# button_brightness_esp32.net
KiCad netlist of a schematic drawn in Altium Designer
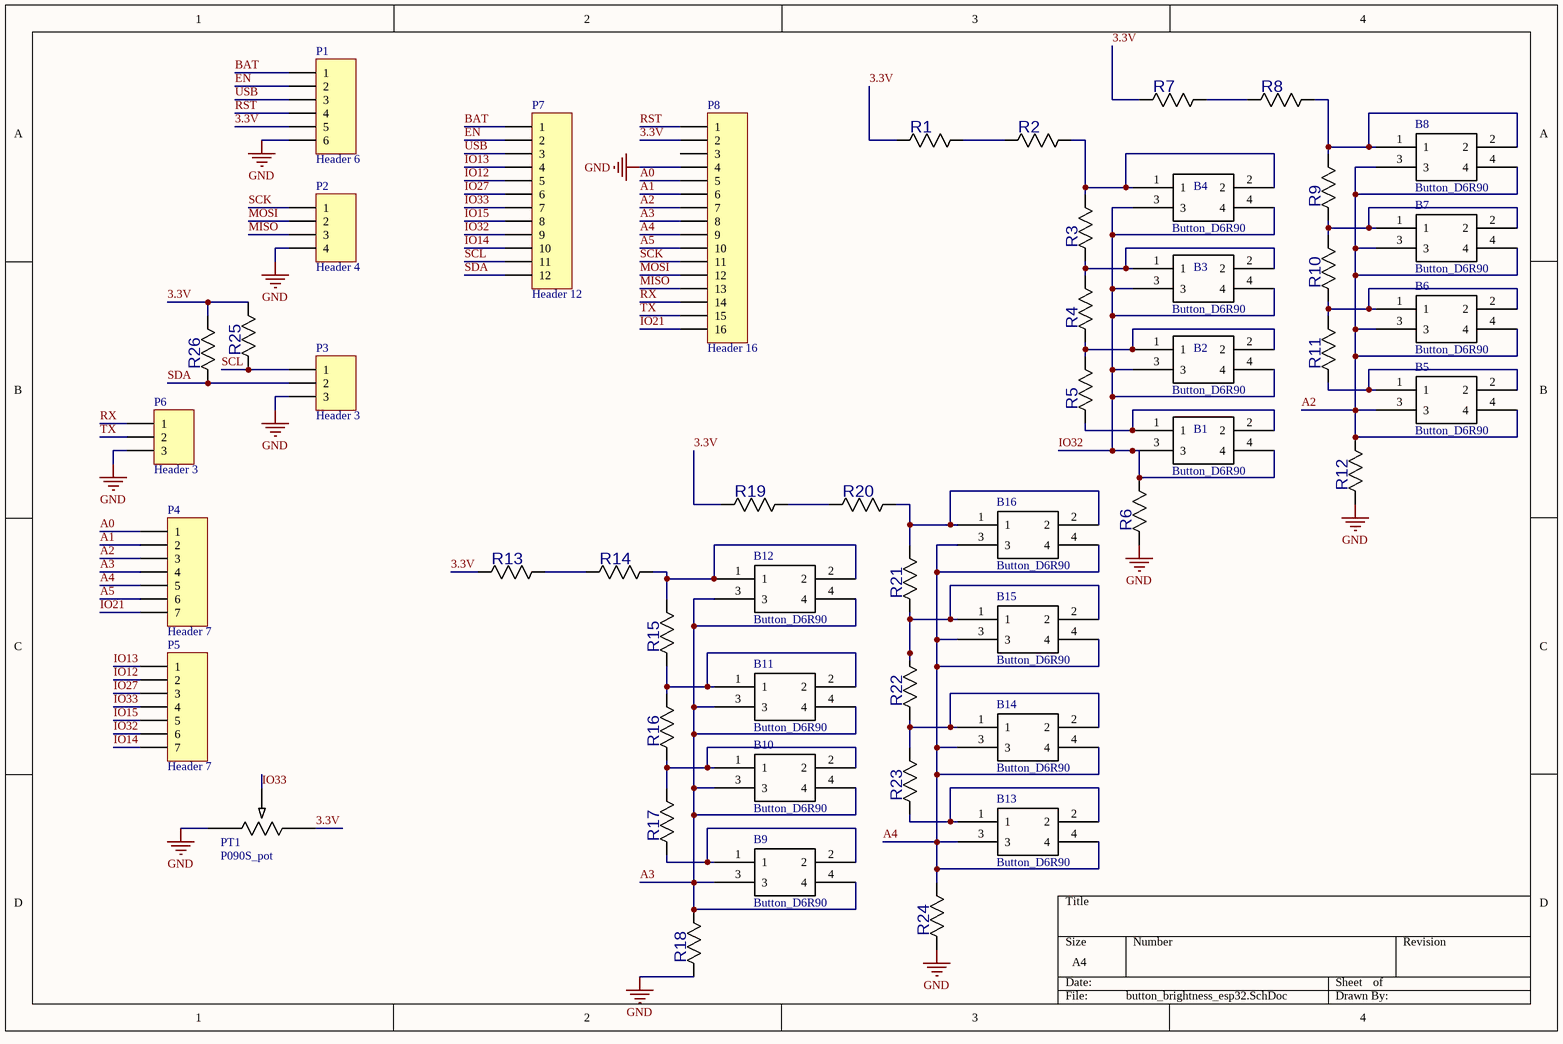
[diagram p0: button_brightness_esp32.SchDoc]

(export (version "E")
  (design (tool "Eeschema 10.0.6"))
  (components
    (comp (ref "B1")
      (value "Button_D6R90")
      (footprint "Button_D6R90")
      (libsource (lib "shematic_lib") (part "Button_D6R90"))
    )
    (comp (ref "B2")
      (value "Button_D6R90")
      (footprint "Button_D6R90")
      (libsource (lib "shematic_lib") (part "Button_D6R90"))
    )
    (comp (ref "B3")
      (value "Button_D6R90")
      (footprint "Button_D6R90")
      (libsource (lib "shematic_lib") (part "Button_D6R90"))
    )
    (comp (ref "B4")
      (value "Button_D6R90")
      (footprint "Button_D6R90")
      (libsource (lib "shematic_lib") (part "Button_D6R90"))
    )
    (comp (ref "B5")
      (value "Button_D6R90")
      (footprint "Button_D6R90")
      (libsource (lib "shematic_lib") (part "Button_D6R90"))
    )
    (comp (ref "B6")
      (value "Button_D6R90")
      (footprint "Button_D6R90")
      (libsource (lib "shematic_lib") (part "Button_D6R90"))
    )
    (comp (ref "B7")
      (value "Button_D6R90")
      (footprint "Button_D6R90")
      (libsource (lib "shematic_lib") (part "Button_D6R90"))
    )
    (comp (ref "B8")
      (value "Button_D6R90")
      (footprint "Button_D6R90")
      (libsource (lib "shematic_lib") (part "Button_D6R90"))
    )
    (comp (ref "B9")
      (value "Button_D6R90")
      (footprint "Button_D6R90")
      (libsource (lib "shematic_lib") (part "Button_D6R90"))
    )
    (comp (ref "B10")
      (value "Button_D6R90")
      (footprint "Button_D6R90")
      (libsource (lib "shematic_lib") (part "Button_D6R90"))
    )
    (comp (ref "B11")
      (value "Button_D6R90")
      (footprint "Button_D6R90")
      (libsource (lib "shematic_lib") (part "Button_D6R90"))
    )
    (comp (ref "B12")
      (value "Button_D6R90")
      (footprint "component_lib:Button_D6R90")
      (libsource (lib "shematic_lib") (part "Button_D6R90"))
    )
    (comp (ref "B13")
      (value "Button_D6R90")
      (footprint "Button_D6R90")
      (libsource (lib "shematic_lib") (part "Button_D6R90"))
    )
    (comp (ref "B14")
      (value "Button_D6R90")
      (footprint "Button_D6R90")
      (libsource (lib "shematic_lib") (part "Button_D6R90"))
    )
    (comp (ref "B15")
      (value "Button_D6R90")
      (footprint "Button_D6R90")
      (libsource (lib "shematic_lib") (part "Button_D6R90"))
    )
    (comp (ref "B16")
      (value "Button_D6R90")
      (footprint "Button_D6R90")
      (libsource (lib "shematic_lib") (part "Button_D6R90"))
    )
    (comp (ref "P1")
      (value "Header 6")
      (footprint "CONN_6")
      (description "Header, 6-Pin")
      (fields (field (name "PUBLISHER") "Altium Limited"))
      (libsource (lib "Miscellaneous Connectors") (part "Header 6"))
    )
    (comp (ref "P2")
      (value "Header 4")
      (footprint "CONN_4")
      (description "Header, 4-Pin")
      (fields (field (name "PUBLISHER") "Altium Limited"))
      (libsource (lib "Miscellaneous Connectors") (part "Header 4"))
    )
    (comp (ref "P3")
      (value "Header 3")
      (footprint "CONN_3")
      (description "Header, 3-Pin")
      (fields (field (name "PUBLISHER") "Altium Limited"))
      (libsource (lib "Miscellaneous Connectors") (part "Header 3"))
    )
    (comp (ref "P4")
      (value "Header 7")
      (footprint "CONN_7")
      (description "Header, 7-Pin")
      (fields (field (name "PUBLISHER") "Altium Limited"))
      (libsource (lib "Miscellaneous Connectors") (part "Header 7"))
    )
    (comp (ref "P5")
      (value "Header 7")
      (footprint "CONN_7")
      (description "Header, 7-Pin")
      (fields (field (name "PUBLISHER") "Altium Limited"))
      (libsource (lib "Miscellaneous Connectors") (part "Header 7"))
    )
    (comp (ref "P6")
      (value "Header 3")
      (footprint "CONN_3")
      (description "Header, 3-Pin")
      (fields (field (name "PUBLISHER") "Altium Limited"))
      (libsource (lib "Miscellaneous Connectors") (part "Header 3"))
    )
    (comp (ref "P7")
      (value "Header 12")
      (footprint "ESP32_feather_short_pins")
      (description "Header, 12-Pin")
      (fields (field (name "PUBLISHER") "Altium Limited"))
      (libsource (lib "Miscellaneous Connectors") (part "Header 12"))
    )
    (comp (ref "P8")
      (value "Header 16")
      (footprint "ESP32_feather_long_pins")
      (description "Header, 16-Pin")
      (fields (field (name "PUBLISHER") "Altium Limited"))
      (libsource (lib "Miscellaneous Connectors") (part "Header 16"))
    )
    (comp (ref "PT1")
      (value "P090S_pot")
      (footprint "POT_PTA3043")
      (libsource (lib "shematic_lib") (part "P090S_pot"))
    )
    (comp (ref "R1")
      (value "ERJ-6GEYJ471V")
      (footprint "component_lib:RES_0804_panasonic")
      (libsource (lib "shematic_lib") (part "ERJ-6GEYJ471V"))
    )
    (comp (ref "R2")
      (value "ERJ-6GEYJ471V")
      (footprint "component_lib:RES_0804_panasonic")
      (libsource (lib "shematic_lib") (part "ERJ-6GEYJ471V"))
    )
    (comp (ref "R3")
      (value "ERJ-6GEYJ471V")
      (footprint "component_lib:RES_0804_panasonic")
      (libsource (lib "shematic_lib") (part "ERJ-6GEYJ471V"))
    )
    (comp (ref "R4")
      (value "ERJ-6GEYJ471V")
      (footprint "component_lib:RES_0804_panasonic")
      (libsource (lib "shematic_lib") (part "ERJ-6GEYJ471V"))
    )
    (comp (ref "R5")
      (value "ERJ-6GEYJ471V")
      (footprint "component_lib:RES_0804_panasonic")
      (libsource (lib "shematic_lib") (part "ERJ-6GEYJ471V"))
    )
    (comp (ref "R6")
      (value "ERJ-6GEYJ471V")
      (footprint "component_lib:RES_0804_panasonic")
      (libsource (lib "shematic_lib") (part "ERJ-6GEYJ471V"))
    )
    (comp (ref "R7")
      (value "ERJ-6GEYJ471V")
      (footprint "component_lib:RES_0804_panasonic")
      (libsource (lib "shematic_lib") (part "ERJ-6GEYJ471V"))
    )
    (comp (ref "R8")
      (value "ERJ-6GEYJ471V")
      (footprint "component_lib:RES_0804_panasonic")
      (libsource (lib "shematic_lib") (part "ERJ-6GEYJ471V"))
    )
    (comp (ref "R9")
      (value "ERJ-6GEYJ471V")
      (footprint "component_lib:RES_0804_panasonic")
      (libsource (lib "shematic_lib") (part "ERJ-6GEYJ471V"))
    )
    (comp (ref "R10")
      (value "ERJ-6GEYJ471V")
      (footprint "component_lib:RES_0804_panasonic")
      (libsource (lib "shematic_lib") (part "ERJ-6GEYJ471V"))
    )
    (comp (ref "R11")
      (value "ERJ-6GEYJ471V")
      (footprint "component_lib:RES_0804_panasonic")
      (libsource (lib "shematic_lib") (part "ERJ-6GEYJ471V"))
    )
    (comp (ref "R12")
      (value "ERJ-6GEYJ471V")
      (footprint "component_lib:RES_0804_panasonic")
      (libsource (lib "shematic_lib") (part "ERJ-6GEYJ471V"))
    )
    (comp (ref "R13")
      (value "ERJ-6GEYJ471V")
      (footprint "component_lib:RES_0804_panasonic")
      (libsource (lib "shematic_lib") (part "ERJ-6GEYJ471V"))
    )
    (comp (ref "R14")
      (value "ERJ-6GEYJ471V")
      (footprint "component_lib:RES_0804_panasonic")
      (libsource (lib "shematic_lib") (part "ERJ-6GEYJ471V"))
    )
    (comp (ref "R15")
      (value "ERJ-6GEYJ471V")
      (footprint "component_lib:RES_0804_panasonic")
      (libsource (lib "shematic_lib") (part "ERJ-6GEYJ471V"))
    )
    (comp (ref "R16")
      (value "ERJ-6GEYJ471V")
      (footprint "component_lib:RES_0804_panasonic")
      (libsource (lib "shematic_lib") (part "ERJ-6GEYJ471V"))
    )
    (comp (ref "R17")
      (value "ERJ-6GEYJ471V")
      (footprint "component_lib:RES_0804_panasonic")
      (libsource (lib "shematic_lib") (part "ERJ-6GEYJ471V"))
    )
    (comp (ref "R18")
      (value "ERJ-6GEYJ471V")
      (footprint "component_lib:RES_0804_panasonic")
      (libsource (lib "shematic_lib") (part "ERJ-6GEYJ471V"))
    )
    (comp (ref "R19")
      (value "ERJ-6GEYJ471V")
      (footprint "component_lib:RES_0804_panasonic")
      (libsource (lib "shematic_lib") (part "ERJ-6GEYJ471V"))
    )
    (comp (ref "R20")
      (value "ERJ-6GEYJ471V")
      (footprint "component_lib:RES_0804_panasonic")
      (libsource (lib "shematic_lib") (part "ERJ-6GEYJ471V"))
    )
    (comp (ref "R21")
      (value "ERJ-6GEYJ471V")
      (footprint "component_lib:RES_0804_panasonic")
      (libsource (lib "shematic_lib") (part "ERJ-6GEYJ471V"))
    )
    (comp (ref "R22")
      (value "ERJ-6GEYJ471V")
      (footprint "component_lib:RES_0804_panasonic")
      (libsource (lib "shematic_lib") (part "ERJ-6GEYJ471V"))
    )
    (comp (ref "R23")
      (value "ERJ-6GEYJ471V")
      (footprint "component_lib:RES_0804_panasonic")
      (libsource (lib "shematic_lib") (part "ERJ-6GEYJ471V"))
    )
    (comp (ref "R24")
      (value "ERJ-6GEYJ471V")
      (footprint "component_lib:RES_0804_panasonic")
      (libsource (lib "shematic_lib") (part "ERJ-6GEYJ471V"))
    )
    (comp (ref "R25")
      (value "ERJ-6GEYJ471V")
      (footprint "component_lib:RES_0804_panasonic")
      (libsource (lib "shematic_lib") (part "ERJ-6GEYJ471V"))
    )
    (comp (ref "R26")
      (value "ERJ-6GEYJ471V")
      (footprint "component_lib:RES_0804_panasonic")
      (libsource (lib "shematic_lib") (part "ERJ-6GEYJ471V"))
    )
  )
  (nets
    (net (code "1") (name "/3.3V") (class "Default")
      (node (ref "P1") (pin "5") (pinfunction "5_5") (pintype "passive"))
      (node (ref "P8") (pin "2") (pinfunction "2_2") (pintype "passive"))
      (node (ref "PT1") (pin "3") (pinfunction "3_3") (pintype "passive"))
      (node (ref "R1") (pin "2") (pinfunction "2_2") (pintype "passive"))
      (node (ref "R13") (pin "2") (pinfunction "2_2") (pintype "passive"))
      (node (ref "R19") (pin "2") (pinfunction "2_2") (pintype "passive"))
      (node (ref "R25") (pin "1") (pinfunction "1_1") (pintype "passive"))
      (node (ref "R26") (pin "1") (pinfunction "1_1") (pintype "passive"))
      (node (ref "R7") (pin "2") (pinfunction "2_2") (pintype "passive"))
    )
    (net (code "2") (name "/A0") (class "Default")
      (node (ref "P4") (pin "1") (pinfunction "1_1") (pintype "passive"))
      (node (ref "P8") (pin "5") (pinfunction "5_5") (pintype "passive"))
    )
    (net (code "3") (name "/A1") (class "Default")
      (node (ref "P4") (pin "2") (pinfunction "2_2") (pintype "passive"))
      (node (ref "P8") (pin "6") (pinfunction "6_6") (pintype "passive"))
    )
    (net (code "4") (name "/A2") (class "Default")
      (node (ref "B5") (pin "3") (pinfunction "3_3") (pintype "passive"))
      (node (ref "B5") (pin "4") (pinfunction "4_4") (pintype "passive"))
      (node (ref "B6") (pin "3") (pinfunction "3_3") (pintype "passive"))
      (node (ref "B6") (pin "4") (pinfunction "4_4") (pintype "passive"))
      (node (ref "B7") (pin "3") (pinfunction "3_3") (pintype "passive"))
      (node (ref "B7") (pin "4") (pinfunction "4_4") (pintype "passive"))
      (node (ref "B8") (pin "3") (pinfunction "3_3") (pintype "passive"))
      (node (ref "B8") (pin "4") (pinfunction "4_4") (pintype "passive"))
      (node (ref "P4") (pin "3") (pinfunction "3_3") (pintype "passive"))
      (node (ref "P8") (pin "7") (pinfunction "7_7") (pintype "passive"))
      (node (ref "R12") (pin "1") (pinfunction "1_1") (pintype "passive"))
    )
    (net (code "5") (name "/A3") (class "Default")
      (node (ref "B10") (pin "3") (pinfunction "3_3") (pintype "passive"))
      (node (ref "B10") (pin "4") (pinfunction "4_4") (pintype "passive"))
      (node (ref "B11") (pin "3") (pinfunction "3_3") (pintype "passive"))
      (node (ref "B11") (pin "4") (pinfunction "4_4") (pintype "passive"))
      (node (ref "B12") (pin "3") (pinfunction "3_3") (pintype "passive"))
      (node (ref "B12") (pin "4") (pinfunction "4_4") (pintype "passive"))
      (node (ref "B9") (pin "3") (pinfunction "3_3") (pintype "passive"))
      (node (ref "B9") (pin "4") (pinfunction "4_4") (pintype "passive"))
      (node (ref "P4") (pin "4") (pinfunction "4_4") (pintype "passive"))
      (node (ref "P8") (pin "8") (pinfunction "8_8") (pintype "passive"))
      (node (ref "R18") (pin "1") (pinfunction "1_1") (pintype "passive"))
    )
    (net (code "6") (name "/A4") (class "Default")
      (node (ref "B13") (pin "3") (pinfunction "3_3") (pintype "passive"))
      (node (ref "B13") (pin "4") (pinfunction "4_4") (pintype "passive"))
      (node (ref "B14") (pin "3") (pinfunction "3_3") (pintype "passive"))
      (node (ref "B14") (pin "4") (pinfunction "4_4") (pintype "passive"))
      (node (ref "B15") (pin "3") (pinfunction "3_3") (pintype "passive"))
      (node (ref "B15") (pin "4") (pinfunction "4_4") (pintype "passive"))
      (node (ref "B16") (pin "3") (pinfunction "3_3") (pintype "passive"))
      (node (ref "B16") (pin "4") (pinfunction "4_4") (pintype "passive"))
      (node (ref "P4") (pin "5") (pinfunction "5_5") (pintype "passive"))
      (node (ref "P8") (pin "9") (pinfunction "9_9") (pintype "passive"))
      (node (ref "R24") (pin "1") (pinfunction "1_1") (pintype "passive"))
    )
    (net (code "7") (name "/A5") (class "Default")
      (node (ref "P4") (pin "6") (pinfunction "6_6") (pintype "passive"))
      (node (ref "P8") (pin "10") (pinfunction "10_10") (pintype "passive"))
    )
    (net (code "8") (name "/BAT") (class "Default")
      (node (ref "P1") (pin "1") (pinfunction "1_1") (pintype "passive"))
      (node (ref "P7") (pin "1") (pinfunction "1_1") (pintype "passive"))
    )
    (net (code "9") (name "/EN") (class "Default")
      (node (ref "P1") (pin "2") (pinfunction "2_2") (pintype "passive"))
      (node (ref "P7") (pin "2") (pinfunction "2_2") (pintype "passive"))
    )
    (net (code "10") (name "/IO12") (class "Default")
      (node (ref "P5") (pin "2") (pinfunction "2_2") (pintype "passive"))
      (node (ref "P7") (pin "5") (pinfunction "5_5") (pintype "passive"))
    )
    (net (code "11") (name "/IO13") (class "Default")
      (node (ref "P5") (pin "1") (pinfunction "1_1") (pintype "passive"))
      (node (ref "P7") (pin "4") (pinfunction "4_4") (pintype "passive"))
    )
    (net (code "12") (name "/IO14") (class "Default")
      (node (ref "P5") (pin "7") (pinfunction "7_7") (pintype "passive"))
      (node (ref "P7") (pin "10") (pinfunction "10_10") (pintype "passive"))
    )
    (net (code "13") (name "/IO15") (class "Default")
      (node (ref "P5") (pin "5") (pinfunction "5_5") (pintype "passive"))
      (node (ref "P7") (pin "8") (pinfunction "8_8") (pintype "passive"))
    )
    (net (code "14") (name "/IO21") (class "Default")
      (node (ref "P4") (pin "7") (pinfunction "7_7") (pintype "passive"))
      (node (ref "P8") (pin "16") (pinfunction "16_16") (pintype "passive"))
    )
    (net (code "15") (name "/IO27") (class "Default")
      (node (ref "P5") (pin "3") (pinfunction "3_3") (pintype "passive"))
      (node (ref "P7") (pin "6") (pinfunction "6_6") (pintype "passive"))
    )
    (net (code "16") (name "/IO32") (class "Default")
      (node (ref "B1") (pin "3") (pinfunction "3_3") (pintype "passive"))
      (node (ref "B1") (pin "4") (pinfunction "4_4") (pintype "passive"))
      (node (ref "B2") (pin "3") (pinfunction "3_3") (pintype "passive"))
      (node (ref "B2") (pin "4") (pinfunction "4_4") (pintype "passive"))
      (node (ref "B3") (pin "3") (pinfunction "3_3") (pintype "passive"))
      (node (ref "B3") (pin "4") (pinfunction "4_4") (pintype "passive"))
      (node (ref "B4") (pin "3") (pinfunction "3_3") (pintype "passive"))
      (node (ref "B4") (pin "4") (pinfunction "4_4") (pintype "passive"))
      (node (ref "P5") (pin "6") (pinfunction "6_6") (pintype "passive"))
      (node (ref "P7") (pin "9") (pinfunction "9_9") (pintype "passive"))
      (node (ref "R6") (pin "1") (pinfunction "1_1") (pintype "passive"))
    )
    (net (code "17") (name "/IO33") (class "Default")
      (node (ref "P5") (pin "4") (pinfunction "4_4") (pintype "passive"))
      (node (ref "P7") (pin "7") (pinfunction "7_7") (pintype "passive"))
      (node (ref "PT1") (pin "2") (pinfunction "2_2") (pintype "passive"))
    )
    (net (code "18") (name "/MISO") (class "Default")
      (node (ref "P2") (pin "3") (pinfunction "3_3") (pintype "passive"))
      (node (ref "P8") (pin "13") (pinfunction "13_13") (pintype "passive"))
    )
    (net (code "19") (name "/MOSI") (class "Default")
      (node (ref "P2") (pin "2") (pinfunction "2_2") (pintype "passive"))
      (node (ref "P8") (pin "12") (pinfunction "12_12") (pintype "passive"))
    )
    (net (code "20") (name "/RST") (class "Default")
      (node (ref "P1") (pin "4") (pinfunction "4_4") (pintype "passive"))
      (node (ref "P8") (pin "1") (pinfunction "1_1") (pintype "passive"))
    )
    (net (code "21") (name "/RX") (class "Default")
      (node (ref "P6") (pin "1") (pinfunction "1_1") (pintype "passive"))
      (node (ref "P8") (pin "14") (pinfunction "14_14") (pintype "passive"))
    )
    (net (code "22") (name "/SCK") (class "Default")
      (node (ref "P2") (pin "1") (pinfunction "1_1") (pintype "passive"))
      (node (ref "P8") (pin "11") (pinfunction "11_11") (pintype "passive"))
    )
    (net (code "23") (name "/SCL") (class "Default")
      (node (ref "P3") (pin "1") (pinfunction "1_1") (pintype "passive"))
      (node (ref "P7") (pin "11") (pinfunction "11_11") (pintype "passive"))
      (node (ref "R25") (pin "2") (pinfunction "2_2") (pintype "passive"))
    )
    (net (code "24") (name "/SDA") (class "Default")
      (node (ref "P3") (pin "2") (pinfunction "2_2") (pintype "passive"))
      (node (ref "P7") (pin "12") (pinfunction "12_12") (pintype "passive"))
      (node (ref "R26") (pin "2") (pinfunction "2_2") (pintype "passive"))
    )
    (net (code "25") (name "/TX") (class "Default")
      (node (ref "P6") (pin "2") (pinfunction "2_2") (pintype "passive"))
      (node (ref "P8") (pin "15") (pinfunction "15_15") (pintype "passive"))
    )
    (net (code "26") (name "/USB") (class "Default")
      (node (ref "P1") (pin "3") (pinfunction "3_3") (pintype "passive"))
      (node (ref "P7") (pin "3") (pinfunction "3_3") (pintype "passive"))
    )
    (net (code "27") (name "GND") (class "Default")
      (node (ref "P1") (pin "6") (pinfunction "6_6") (pintype "passive"))
      (node (ref "P2") (pin "4") (pinfunction "4_4") (pintype "passive"))
      (node (ref "P3") (pin "3") (pinfunction "3_3") (pintype "passive"))
      (node (ref "P6") (pin "3") (pinfunction "3_3") (pintype "passive"))
      (node (ref "P8") (pin "4") (pinfunction "4_4") (pintype "passive"))
      (node (ref "PT1") (pin "1") (pinfunction "1_1") (pintype "passive"))
      (node (ref "R12") (pin "2") (pinfunction "2_2") (pintype "passive"))
      (node (ref "R18") (pin "2") (pinfunction "2_2") (pintype "passive"))
      (node (ref "R24") (pin "2") (pinfunction "2_2") (pintype "passive"))
      (node (ref "R6") (pin "2") (pinfunction "2_2") (pintype "passive"))
    )
    (net (code "28") (name "Net-(B1-Pad1)") (class "Default")
      (node (ref "B1") (pin "1") (pinfunction "1_1") (pintype "passive"))
      (node (ref "B1") (pin "2") (pinfunction "2_2") (pintype "passive"))
      (node (ref "R5") (pin "2") (pinfunction "2_2") (pintype "passive"))
    )
    (net (code "29") (name "Net-(B2-Pad1)") (class "Default")
      (node (ref "B2") (pin "1") (pinfunction "1_1") (pintype "passive"))
      (node (ref "B2") (pin "2") (pinfunction "2_2") (pintype "passive"))
      (node (ref "R4") (pin "2") (pinfunction "2_2") (pintype "passive"))
      (node (ref "R5") (pin "1") (pinfunction "1_1") (pintype "passive"))
    )
    (net (code "30") (name "Net-(B3-Pad1)") (class "Default")
      (node (ref "B3") (pin "1") (pinfunction "1_1") (pintype "passive"))
      (node (ref "B3") (pin "2") (pinfunction "2_2") (pintype "passive"))
      (node (ref "R3") (pin "2") (pinfunction "2_2") (pintype "passive"))
      (node (ref "R4") (pin "1") (pinfunction "1_1") (pintype "passive"))
    )
    (net (code "31") (name "Net-(B4-Pad1)") (class "Default")
      (node (ref "B4") (pin "1") (pinfunction "1_1") (pintype "passive"))
      (node (ref "B4") (pin "2") (pinfunction "2_2") (pintype "passive"))
      (node (ref "R2") (pin "1") (pinfunction "1_1") (pintype "passive"))
      (node (ref "R3") (pin "1") (pinfunction "1_1") (pintype "passive"))
    )
    (net (code "32") (name "Net-(B5-Pad1)") (class "Default")
      (node (ref "B5") (pin "1") (pinfunction "1_1") (pintype "passive"))
      (node (ref "B5") (pin "2") (pinfunction "2_2") (pintype "passive"))
      (node (ref "R11") (pin "2") (pinfunction "2_2") (pintype "passive"))
    )
    (net (code "33") (name "Net-(B6-Pad1)") (class "Default")
      (node (ref "B6") (pin "1") (pinfunction "1_1") (pintype "passive"))
      (node (ref "B6") (pin "2") (pinfunction "2_2") (pintype "passive"))
      (node (ref "R10") (pin "2") (pinfunction "2_2") (pintype "passive"))
      (node (ref "R11") (pin "1") (pinfunction "1_1") (pintype "passive"))
    )
    (net (code "34") (name "Net-(B7-Pad1)") (class "Default")
      (node (ref "B7") (pin "1") (pinfunction "1_1") (pintype "passive"))
      (node (ref "B7") (pin "2") (pinfunction "2_2") (pintype "passive"))
      (node (ref "R10") (pin "1") (pinfunction "1_1") (pintype "passive"))
      (node (ref "R9") (pin "2") (pinfunction "2_2") (pintype "passive"))
    )
    (net (code "35") (name "Net-(B8-Pad1)") (class "Default")
      (node (ref "B8") (pin "1") (pinfunction "1_1") (pintype "passive"))
      (node (ref "B8") (pin "2") (pinfunction "2_2") (pintype "passive"))
      (node (ref "R8") (pin "1") (pinfunction "1_1") (pintype "passive"))
      (node (ref "R9") (pin "1") (pinfunction "1_1") (pintype "passive"))
    )
    (net (code "36") (name "Net-(B9-Pad1)") (class "Default")
      (node (ref "B9") (pin "1") (pinfunction "1_1") (pintype "passive"))
      (node (ref "B9") (pin "2") (pinfunction "2_2") (pintype "passive"))
      (node (ref "R17") (pin "2") (pinfunction "2_2") (pintype "passive"))
    )
    (net (code "37") (name "Net-(B10-Pad1)") (class "Default")
      (node (ref "B10") (pin "1") (pinfunction "1_1") (pintype "passive"))
      (node (ref "B10") (pin "2") (pinfunction "2_2") (pintype "passive"))
      (node (ref "R16") (pin "2") (pinfunction "2_2") (pintype "passive"))
      (node (ref "R17") (pin "1") (pinfunction "1_1") (pintype "passive"))
    )
    (net (code "38") (name "Net-(B11-Pad1)") (class "Default")
      (node (ref "B11") (pin "1") (pinfunction "1_1") (pintype "passive"))
      (node (ref "B11") (pin "2") (pinfunction "2_2") (pintype "passive"))
      (node (ref "R15") (pin "2") (pinfunction "2_2") (pintype "passive"))
      (node (ref "R16") (pin "1") (pinfunction "1_1") (pintype "passive"))
    )
    (net (code "39") (name "Net-(B12-Pad1)") (class "Default")
      (node (ref "B12") (pin "1") (pinfunction "1_1") (pintype "passive"))
      (node (ref "B12") (pin "2") (pinfunction "2_2") (pintype "passive"))
      (node (ref "R14") (pin "1") (pinfunction "1_1") (pintype "passive"))
      (node (ref "R15") (pin "1") (pinfunction "1_1") (pintype "passive"))
    )
    (net (code "40") (name "Net-(B13-Pad1)") (class "Default")
      (node (ref "B13") (pin "1") (pinfunction "1_1") (pintype "passive"))
      (node (ref "B13") (pin "2") (pinfunction "2_2") (pintype "passive"))
      (node (ref "R23") (pin "2") (pinfunction "2_2") (pintype "passive"))
    )
    (net (code "41") (name "Net-(B14-Pad1)") (class "Default")
      (node (ref "B14") (pin "1") (pinfunction "1_1") (pintype "passive"))
      (node (ref "B14") (pin "2") (pinfunction "2_2") (pintype "passive"))
      (node (ref "R22") (pin "2") (pinfunction "2_2") (pintype "passive"))
      (node (ref "R23") (pin "1") (pinfunction "1_1") (pintype "passive"))
    )
    (net (code "42") (name "Net-(B15-Pad1)") (class "Default")
      (node (ref "B15") (pin "1") (pinfunction "1_1") (pintype "passive"))
      (node (ref "B15") (pin "2") (pinfunction "2_2") (pintype "passive"))
      (node (ref "R21") (pin "2") (pinfunction "2_2") (pintype "passive"))
      (node (ref "R22") (pin "1") (pinfunction "1_1") (pintype "passive"))
    )
    (net (code "43") (name "Net-(B16-Pad1)") (class "Default")
      (node (ref "B16") (pin "1") (pinfunction "1_1") (pintype "passive"))
      (node (ref "B16") (pin "2") (pinfunction "2_2") (pintype "passive"))
      (node (ref "R20") (pin "1") (pinfunction "1_1") (pintype "passive"))
      (node (ref "R21") (pin "1") (pinfunction "1_1") (pintype "passive"))
    )
    (net (code "44") (name "Net-(R1-Pad1)") (class "Default")
      (node (ref "R1") (pin "1") (pinfunction "1_1") (pintype "passive"))
      (node (ref "R2") (pin "2") (pinfunction "2_2") (pintype "passive"))
    )
    (net (code "45") (name "Net-(R7-Pad1)") (class "Default")
      (node (ref "R7") (pin "1") (pinfunction "1_1") (pintype "passive"))
      (node (ref "R8") (pin "2") (pinfunction "2_2") (pintype "passive"))
    )
    (net (code "46") (name "Net-(R13-Pad1)") (class "Default")
      (node (ref "R13") (pin "1") (pinfunction "1_1") (pintype "passive"))
      (node (ref "R14") (pin "2") (pinfunction "2_2") (pintype "passive"))
    )
    (net (code "47") (name "Net-(R19-Pad1)") (class "Default")
      (node (ref "R19") (pin "1") (pinfunction "1_1") (pintype "passive"))
      (node (ref "R20") (pin "2") (pinfunction "2_2") (pintype "passive"))
    )
    (net (code "48") (name "unconnected-(P8-Pad3)") (class "Default")
      (node (ref "P8") (pin "3") (pinfunction "3_3") (pintype "passive"))
    )
  )
)
